# RS232.net
KiCad netlist of a schematic drawn in Altium Designer
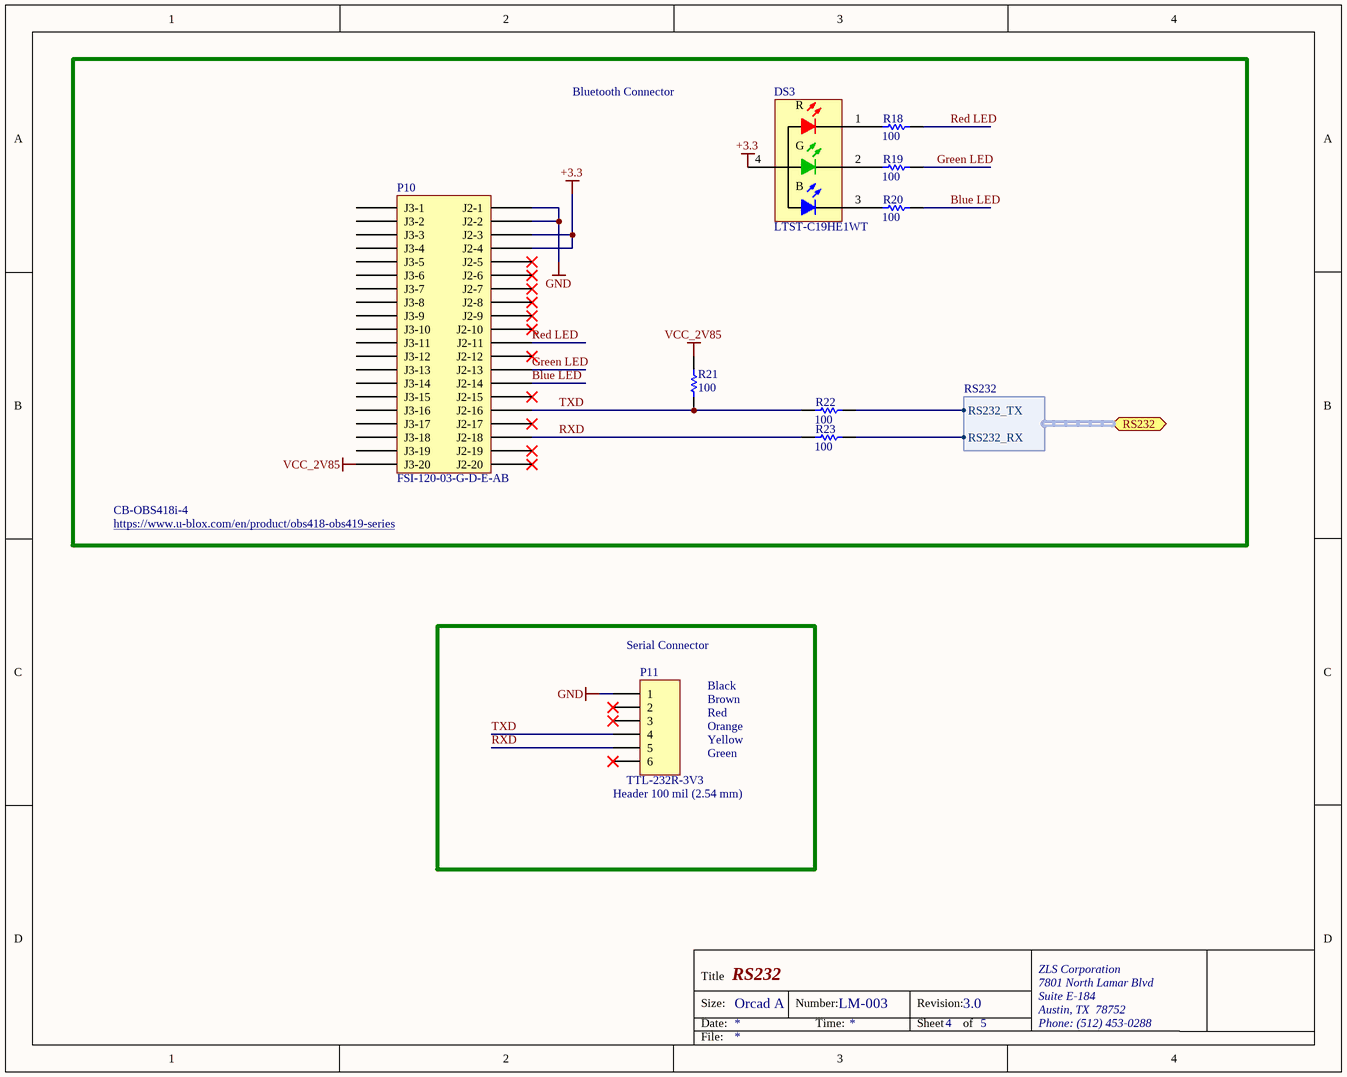
[diagram p0: RS232.SchDoc]

(export (version "E")
  (design (tool "Eeschema 10.0.6"))
  (components
    (comp (ref "DS3")
      (value "LTST-C19HE1WT")
      (footprint "LTST-C19HE1WT-4_V")
      (description "LED Tri-Color Blue/Green/Red, 5 V, -20 to 80 degC, 4-Pin SMD, RoHS, Tape and Reel")
      (fields (field (name "MANUFACTURER") "Lite-On"))
      (libsource (lib "Altium Content Vault") (part "LTST-C19HE1WT-4"))
    )
    (comp (ref "P10")
      (value "FSI-120-03-G-D-E-AB")
      (footprint "FSI-120-03-G-D-E-AB")
      (fields (field (name "SUPPLIER PART NUMBER 1") "FSI-120-03-G-D-E-AB"))
      (libsource (lib "ZLS_Schematic_lib") (part "FSI-120-03-G-D-E-AB"))
    )
    (comp (ref "P11")
      (value "Header 100 mil (2.54 mm)")
      (footprint "HDR1X6")
      (description "CABLE USB SERIAL 3.3V 2MM HEADER")
      (libsource (lib "Miscellaneous Connectors") (part "Header 6H"))
    )
    (comp (ref "R18")
      (value "100")
      (footprint "RESC0402(1005)_M")
      (libsource (lib "Altium Content Vault") (part "CMP-1011-00651-1"))
    )
    (comp (ref "R19")
      (value "100")
      (footprint "RESC0402(1005)_M")
      (libsource (lib "Altium Content Vault") (part "CMP-1011-00651-1"))
    )
    (comp (ref "R20")
      (value "100")
      (footprint "RESC0402(1005)_M")
      (libsource (lib "Altium Content Vault") (part "CMP-1011-00651-1"))
    )
    (comp (ref "R21")
      (value "100")
      (footprint "RESC0402(1005)_M")
      (libsource (lib "Altium Content Vault") (part "CMP-1011-00651-1"))
    )
    (comp (ref "R22")
      (value "100")
      (footprint "RESC0402(1005)_M")
      (libsource (lib "Altium Content Vault") (part "CMP-1011-00651-1"))
    )
    (comp (ref "R23")
      (value "100")
      (footprint "RESC0402(1005)_M")
      (libsource (lib "Altium Content Vault") (part "CMP-1011-00651-1"))
    )
  )
  (nets
    (net (code "2") (name "+3.3") (class "Default")
      (node (ref "DS3") (pin "4") (pinfunction "A_4") (pintype "passive"))
      (node (ref "P10") (pin "J2-3") (pinfunction "J2-3_J2-3") (pintype "passive"))
      (node (ref "P10") (pin "J2-4") (pinfunction "J2-4_J2-4") (pintype "passive"))
    )
    (net (code "3") (name "/Blue LED") (class "Default")
      (node (ref "P10") (pin "J2-14") (pinfunction "J2-14_J2-14") (pintype "passive"))
      (node (ref "R20") (pin "2") (pinfunction "2_2") (pintype "passive"))
    )
    (net (code "4") (name "/Green LED") (class "Default")
      (node (ref "P10") (pin "J2-13") (pinfunction "J2-13_J2-13") (pintype "passive"))
      (node (ref "R19") (pin "2") (pinfunction "2_2") (pintype "passive"))
    )
    (net (code "5") (name "/RS232_RX") (class "Default")
      (node (ref "R23") (pin "2") (pinfunction "2_2") (pintype "passive"))
    )
    (net (code "6") (name "/RS232_TX") (class "Default")
      (node (ref "R22") (pin "2") (pinfunction "2_2") (pintype "passive"))
    )
    (net (code "7") (name "/RXD") (class "Default")
      (node (ref "P10") (pin "J2-18") (pinfunction "J2-18_J2-18") (pintype "passive"))
      (node (ref "P11") (pin "5") (pinfunction "5_5") (pintype "passive"))
      (node (ref "R23") (pin "1") (pinfunction "1_1") (pintype "passive"))
    )
    (net (code "8") (name "/Red LED") (class "Default")
      (node (ref "P10") (pin "J2-11") (pinfunction "J2-11_J2-11") (pintype "passive"))
      (node (ref "R18") (pin "2") (pinfunction "2_2") (pintype "passive"))
    )
    (net (code "9") (name "/TXD") (class "Default")
      (node (ref "P10") (pin "J2-16") (pinfunction "J2-16_J2-16") (pintype "passive"))
      (node (ref "P11") (pin "4") (pinfunction "4_4") (pintype "passive"))
      (node (ref "R21") (pin "1") (pinfunction "1_1") (pintype "passive"))
      (node (ref "R22") (pin "1") (pinfunction "1_1") (pintype "passive"))
    )
    (net (code "11") (name "GND") (class "Default")
      (node (ref "P10") (pin "J2-1") (pinfunction "J2-1_J2-1") (pintype "passive"))
      (node (ref "P10") (pin "J2-2") (pinfunction "J2-2_J2-2") (pintype "passive"))
      (node (ref "P11") (pin "1") (pinfunction "1_1") (pintype "passive"))
    )
    (net (code "12") (name "Net-(DS3-B)") (class "Default")
      (node (ref "DS3") (pin "3") (pinfunction "B_3") (pintype "passive"))
      (node (ref "R20") (pin "1") (pinfunction "1_1") (pintype "passive"))
    )
    (net (code "13") (name "Net-(DS3-G)") (class "Default")
      (node (ref "DS3") (pin "2") (pinfunction "G_2") (pintype "passive"))
      (node (ref "R19") (pin "1") (pinfunction "1_1") (pintype "passive"))
    )
    (net (code "14") (name "Net-(DS3-R)") (class "Default")
      (node (ref "DS3") (pin "1") (pinfunction "R_1") (pintype "passive"))
      (node (ref "R18") (pin "1") (pinfunction "1_1") (pintype "passive"))
    )
    (net (code "15") (name "VCC_2V85") (class "Default")
      (node (ref "P10") (pin "J3-20") (pinfunction "J3-20_J3-20") (pintype "passive"))
      (node (ref "R21") (pin "2") (pinfunction "2_2") (pintype "passive"))
    )
    (net (code "16") (name "unconnected-(P10-PadJ2-5)") (class "Default")
      (node (ref "P10") (pin "J2-5") (pinfunction "J2-5_J2-5") (pintype "passive+no_connect"))
    )
    (net (code "17") (name "unconnected-(P10-PadJ2-6)") (class "Default")
      (node (ref "P10") (pin "J2-6") (pinfunction "J2-6_J2-6") (pintype "passive+no_connect"))
    )
    (net (code "18") (name "unconnected-(P10-PadJ2-7)") (class "Default")
      (node (ref "P10") (pin "J2-7") (pinfunction "J2-7_J2-7") (pintype "passive+no_connect"))
    )
    (net (code "19") (name "unconnected-(P10-PadJ2-8)") (class "Default")
      (node (ref "P10") (pin "J2-8") (pinfunction "J2-8_J2-8") (pintype "passive+no_connect"))
    )
    (net (code "20") (name "unconnected-(P10-PadJ2-9)") (class "Default")
      (node (ref "P10") (pin "J2-9") (pinfunction "J2-9_J2-9") (pintype "passive+no_connect"))
    )
    (net (code "21") (name "unconnected-(P10-PadJ2-10)") (class "Default")
      (node (ref "P10") (pin "J2-10") (pinfunction "J2-10_J2-10") (pintype "passive+no_connect"))
    )
    (net (code "22") (name "unconnected-(P10-PadJ2-12)") (class "Default")
      (node (ref "P10") (pin "J2-12") (pinfunction "J2-12_J2-12") (pintype "passive+no_connect"))
    )
    (net (code "23") (name "unconnected-(P10-PadJ2-15)") (class "Default")
      (node (ref "P10") (pin "J2-15") (pinfunction "J2-15_J2-15") (pintype "passive+no_connect"))
    )
    (net (code "24") (name "unconnected-(P10-PadJ2-17)") (class "Default")
      (node (ref "P10") (pin "J2-17") (pinfunction "J2-17_J2-17") (pintype "passive+no_connect"))
    )
    (net (code "25") (name "unconnected-(P10-PadJ2-19)") (class "Default")
      (node (ref "P10") (pin "J2-19") (pinfunction "J2-19_J2-19") (pintype "passive+no_connect"))
    )
    (net (code "26") (name "unconnected-(P10-PadJ2-20)") (class "Default")
      (node (ref "P10") (pin "J2-20") (pinfunction "J2-20_J2-20") (pintype "passive+no_connect"))
    )
    (net (code "27") (name "unconnected-(P10-PadJ3-1)") (class "Default")
      (node (ref "P10") (pin "J3-1") (pinfunction "J3-1_J3-1") (pintype "passive"))
    )
    (net (code "28") (name "unconnected-(P10-PadJ3-2)") (class "Default")
      (node (ref "P10") (pin "J3-2") (pinfunction "J3-2_J3-2") (pintype "passive"))
    )
    (net (code "29") (name "unconnected-(P10-PadJ3-3)") (class "Default")
      (node (ref "P10") (pin "J3-3") (pinfunction "J3-3_J3-3") (pintype "passive"))
    )
    (net (code "30") (name "unconnected-(P10-PadJ3-4)") (class "Default")
      (node (ref "P10") (pin "J3-4") (pinfunction "J3-4_J3-4") (pintype "passive"))
    )
    (net (code "31") (name "unconnected-(P10-PadJ3-5)") (class "Default")
      (node (ref "P10") (pin "J3-5") (pinfunction "J3-5_J3-5") (pintype "passive"))
    )
    (net (code "32") (name "unconnected-(P10-PadJ3-6)") (class "Default")
      (node (ref "P10") (pin "J3-6") (pinfunction "J3-6_J3-6") (pintype "passive"))
    )
    (net (code "33") (name "unconnected-(P10-PadJ3-7)") (class "Default")
      (node (ref "P10") (pin "J3-7") (pinfunction "J3-7_J3-7") (pintype "passive"))
    )
    (net (code "34") (name "unconnected-(P10-PadJ3-8)") (class "Default")
      (node (ref "P10") (pin "J3-8") (pinfunction "J3-8_J3-8") (pintype "passive"))
    )
    (net (code "35") (name "unconnected-(P10-PadJ3-9)") (class "Default")
      (node (ref "P10") (pin "J3-9") (pinfunction "J3-9_J3-9") (pintype "passive"))
    )
    (net (code "36") (name "unconnected-(P10-PadJ3-10)") (class "Default")
      (node (ref "P10") (pin "J3-10") (pinfunction "J3-10_J3-10") (pintype "passive"))
    )
    (net (code "37") (name "unconnected-(P10-PadJ3-11)") (class "Default")
      (node (ref "P10") (pin "J3-11") (pinfunction "J3-11_J3-11") (pintype "passive"))
    )
    (net (code "38") (name "unconnected-(P10-PadJ3-12)") (class "Default")
      (node (ref "P10") (pin "J3-12") (pinfunction "J3-12_J3-12") (pintype "passive"))
    )
    (net (code "39") (name "unconnected-(P10-PadJ3-13)") (class "Default")
      (node (ref "P10") (pin "J3-13") (pinfunction "J3-13_J3-13") (pintype "passive"))
    )
    (net (code "40") (name "unconnected-(P10-PadJ3-14)") (class "Default")
      (node (ref "P10") (pin "J3-14") (pinfunction "J3-14_J3-14") (pintype "passive"))
    )
    (net (code "41") (name "unconnected-(P10-PadJ3-15)") (class "Default")
      (node (ref "P10") (pin "J3-15") (pinfunction "J3-15_J3-15") (pintype "passive"))
    )
    (net (code "42") (name "unconnected-(P10-PadJ3-16)") (class "Default")
      (node (ref "P10") (pin "J3-16") (pinfunction "J3-16_J3-16") (pintype "passive"))
    )
    (net (code "43") (name "unconnected-(P10-PadJ3-17)") (class "Default")
      (node (ref "P10") (pin "J3-17") (pinfunction "J3-17_J3-17") (pintype "passive"))
    )
    (net (code "44") (name "unconnected-(P10-PadJ3-18)") (class "Default")
      (node (ref "P10") (pin "J3-18") (pinfunction "J3-18_J3-18") (pintype "passive"))
    )
    (net (code "45") (name "unconnected-(P10-PadJ3-19)") (class "Default")
      (node (ref "P10") (pin "J3-19") (pinfunction "J3-19_J3-19") (pintype "passive"))
    )
    (net (code "46") (name "unconnected-(P11-Pad2)") (class "Default")
      (node (ref "P11") (pin "2") (pinfunction "2_2") (pintype "passive+no_connect"))
    )
    (net (code "47") (name "unconnected-(P11-Pad3)") (class "Default")
      (node (ref "P11") (pin "3") (pinfunction "3_3") (pintype "passive+no_connect"))
    )
    (net (code "48") (name "unconnected-(P11-Pad6)") (class "Default")
      (node (ref "P11") (pin "6") (pinfunction "6_6") (pintype "passive+no_connect"))
    )
  )
)
